# P5_ACCEL.net
KiCad netlist of a schematic drawn in Altium Designer
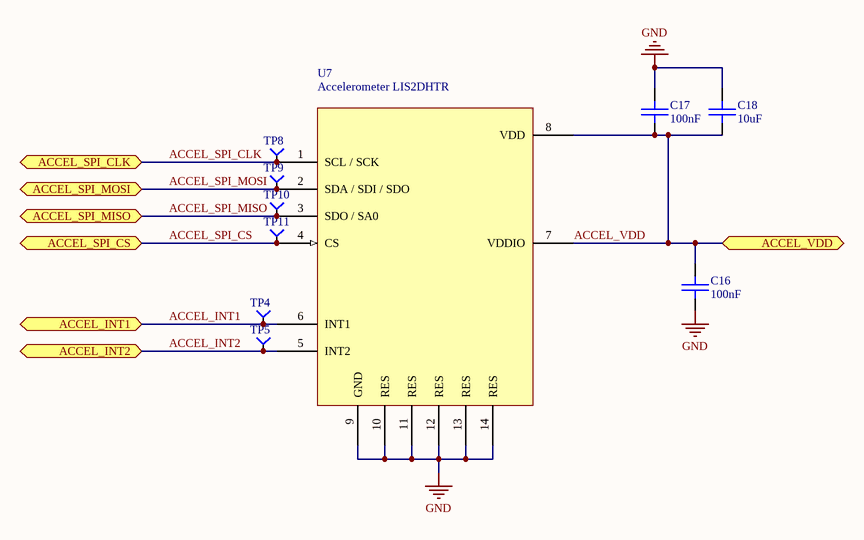
[diagram p0: P5_ACCEL.SchDoc]

(export (version "E")
  (design (tool "Eeschema 10.0.6"))
  (components
    (comp (ref "C16")
      (value "100nF")
      (footprint "CAPC0201(0603)_N")
      (fields (field (name "TOLERANCE") "+/-10%") (field (name "Comment") "CAP CER 0.1UF 10V 10% X5R 0201"))
      (libsource (lib "Arena_Lib") (part "CAP"))
    )
    (comp (ref "C17")
      (value "100nF")
      (footprint "CAPC0201(0603)_N")
      (fields (field (name "TOLERANCE") "+/-10%") (field (name "Comment") "CAP CER 0.1UF 10V 10% X5R 0201"))
      (libsource (lib "Arena_Lib") (part "CAP"))
    )
    (comp (ref "C18")
      (value "10uF")
      (footprint "CAPC0603(1608)_N")
      (fields (field (name "TOLERANCE") "+/-20%") (field (name "Comment") "CAP CER 10UF 6.3V 20% X5R 0603"))
      (libsource (lib "Arena_Lib") (part "CAP"))
    )
    (comp (ref "TP4")
      (value "TEST POINT 5MILx20MIL")
      (footprint "SMT_TP_5milx20mil")
      (description "Test Point")
      (libsource (lib "Arena_Lib") (part "TP"))
    )
    (comp (ref "TP5")
      (value "TEST POINT 5MILx20MIL")
      (footprint "SMT_TP_5milx20mil")
      (description "Test Point")
      (libsource (lib "Arena_Lib") (part "TP"))
    )
    (comp (ref "TP8")
      (value "TEST POINT 5MILx20MIL")
      (footprint "SMT_TP_5milx20mil")
      (description "Test Point")
      (libsource (lib "Arena_Lib") (part "TP"))
    )
    (comp (ref "TP9")
      (value "TEST POINT 5MILx20MIL")
      (footprint "SMT_TP_5milx20mil")
      (description "Test Point")
      (libsource (lib "Arena_Lib") (part "TP"))
    )
    (comp (ref "TP10")
      (value "TEST POINT 5MILx20MIL")
      (footprint "SMT_TP_5milx20mil")
      (description "Test Point")
      (libsource (lib "Arena_Lib") (part "TP"))
    )
    (comp (ref "TP11")
      (value "TEST POINT 5MILx20MIL")
      (footprint "SMT_TP_5milx20mil")
      (description "Test Point")
      (libsource (lib "Arena_Lib") (part "TP"))
    )
    (comp (ref "U7")
      (value "Accelerometer LIS2DHTR")
      (footprint "LGA14N")
      (description "STMicro 3-axis accelerometer")
      (libsource (lib "Arena_Lib") (part "LIS2DH"))
    )
  )
  (nets
    (net (code "1") (name "/ACCEL_INT1") (class "Default")
      (node (ref "TP4") (pin "1") (pinfunction "TP_1") (pintype "passive"))
      (node (ref "U7") (pin "6") (pinfunction "INT1_6") (pintype "passive"))
    )
    (net (code "2") (name "/ACCEL_INT2") (class "Default")
      (node (ref "TP5") (pin "1") (pinfunction "TP_1") (pintype "passive"))
      (node (ref "U7") (pin "5") (pinfunction "INT2_5") (pintype "power_in"))
    )
    (net (code "3") (name "/ACCEL_SPI_CLK") (class "Default")
      (node (ref "TP8") (pin "1") (pinfunction "TP_1") (pintype "passive"))
      (node (ref "U7") (pin "1") (pinfunction "SCL_/_SCK_1") (pintype "passive"))
    )
    (net (code "4") (name "/ACCEL_SPI_CS") (class "Default")
      (node (ref "TP11") (pin "1") (pinfunction "TP_1") (pintype "passive"))
      (node (ref "U7") (pin "4") (pinfunction "CS_4") (pintype "input"))
    )
    (net (code "5") (name "/ACCEL_SPI_MISO") (class "Default")
      (node (ref "TP10") (pin "1") (pinfunction "TP_1") (pintype "passive"))
      (node (ref "U7") (pin "3") (pinfunction "SDO_/_SA0_3") (pintype "passive"))
    )
    (net (code "6") (name "/ACCEL_SPI_MOSI") (class "Default")
      (node (ref "TP9") (pin "1") (pinfunction "TP_1") (pintype "passive"))
      (node (ref "U7") (pin "2") (pinfunction "SDA_/_SDI_/_SDO_2") (pintype "passive"))
    )
    (net (code "7") (name "/ACCEL_VDD") (class "Default")
      (node (ref "C16") (pin "2") (pinfunction "2_2") (pintype "passive"))
      (node (ref "C17") (pin "1") (pinfunction "1_1") (pintype "passive"))
      (node (ref "C18") (pin "1") (pinfunction "1_1") (pintype "passive"))
      (node (ref "U7") (pin "7") (pinfunction "VDDIO_7") (pintype "power_in"))
      (node (ref "U7") (pin "8") (pinfunction "VDD_8") (pintype "power_in"))
    )
    (net (code "8") (name "GND") (class "Default")
      (node (ref "C16") (pin "1") (pinfunction "1_1") (pintype "passive"))
      (node (ref "C17") (pin "2") (pinfunction "2_2") (pintype "passive"))
      (node (ref "C18") (pin "2") (pinfunction "2_2") (pintype "passive"))
      (node (ref "U7") (pin "10") (pinfunction "RES_10") (pintype "passive"))
      (node (ref "U7") (pin "11") (pinfunction "RES_11") (pintype "passive"))
      (node (ref "U7") (pin "12") (pinfunction "RES_12") (pintype "power_in"))
      (node (ref "U7") (pin "13") (pinfunction "RES_13") (pintype "passive"))
      (node (ref "U7") (pin "14") (pinfunction "RES_14") (pintype "power_in"))
      (node (ref "U7") (pin "9") (pinfunction "GND_9") (pintype "passive"))
    )
  )
)
